# design.net
KiCad netlist of a schematic drawn in Altium Designer
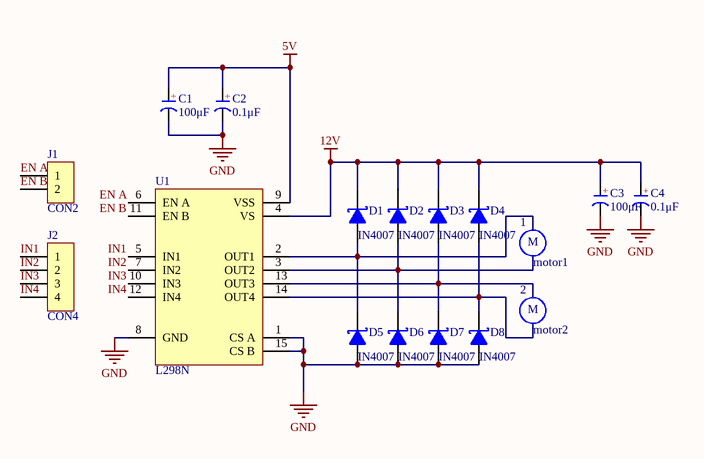
[diagram p0: 电机驱动原理图.SchDoc]

(export (version "E")
  (design (tool "Eeschema 10.0.6"))
  (components
    (comp (ref "1") (value "motor1") (libsource (lib "Schlib1") (part "电机")))
    (comp (ref "2") (value "motor2") (libsource (lib "Schlib1") (part "电机")))
    (comp (ref "C1") (value "100μF") (libsource (lib "Schlib1") (part "极性电容")))
    (comp (ref "C2") (value "0.1μF") (libsource (lib "Schlib1") (part "极性电容")))
    (comp (ref "C3") (value "100μF") (libsource (lib "Schlib1") (part "极性电容")))
    (comp (ref "C4") (value "0.1μF") (libsource (lib "Schlib1") (part "极性电容")))
    (comp (ref "D1") (value "IN4007") (libsource (lib "Schlib1") (part "肖特基二极管")))
    (comp (ref "D2") (value "IN4007") (libsource (lib "Schlib1") (part "肖特基二极管")))
    (comp (ref "D3") (value "IN4007") (libsource (lib "Schlib1") (part "肖特基二极管")))
    (comp (ref "D4") (value "IN4007") (libsource (lib "Schlib1") (part "肖特基二极管")))
    (comp (ref "D5") (value "IN4007") (libsource (lib "Schlib1") (part "肖特基二极管")))
    (comp (ref "D6") (value "IN4007") (libsource (lib "Schlib1") (part "肖特基二极管")))
    (comp (ref "D7") (value "IN4007") (libsource (lib "Schlib1") (part "肖特基二极管")))
    (comp (ref "D8") (value "IN4007") (libsource (lib "Schlib1") (part "肖特基二极管")))
    (comp (ref "J1")
      (value "CON2")
      (footprint "2PIN杜邦插座_1.27mm")
      (description "Connector")
      (libsource (lib "智能车主板") (part "CON2"))
    )
    (comp (ref "J2")
      (value "CON4")
      (footprint "HDR1X4")
      (description "Connector")
      (libsource (lib "智能车主板") (part "CON4"))
    )
    (comp (ref "U1") (value "L298N") (libsource (lib "Schlib1") (part "L298N")))
  )
  (nets
    (net (code "1") (name "/EN A") (class "Default")
      (node (ref "J1") (pin "1") (pinfunction "1_1") (pintype "passive"))
      (node (ref "U1") (pin "6") (pinfunction "EN_A_6") (pintype "passive"))
    )
    (net (code "2") (name "/EN B") (class "Default")
      (node (ref "J1") (pin "2") (pinfunction "2_2") (pintype "passive"))
      (node (ref "U1") (pin "11") (pinfunction "EN_B_11") (pintype "passive"))
    )
    (net (code "3") (name "/IN1") (class "Default")
      (node (ref "J2") (pin "1") (pinfunction "1_1") (pintype "passive"))
      (node (ref "U1") (pin "5") (pinfunction "IN1_5") (pintype "passive"))
    )
    (net (code "4") (name "/IN2") (class "Default")
      (node (ref "J2") (pin "2") (pinfunction "2_2") (pintype "passive"))
      (node (ref "U1") (pin "7") (pinfunction "IN2_7") (pintype "passive"))
    )
    (net (code "5") (name "/IN3") (class "Default")
      (node (ref "J2") (pin "3") (pinfunction "3_3") (pintype "passive"))
      (node (ref "U1") (pin "10") (pinfunction "IN3_10") (pintype "passive"))
    )
    (net (code "6") (name "/IN4") (class "Default")
      (node (ref "J2") (pin "4") (pinfunction "4_4") (pintype "passive"))
      (node (ref "U1") (pin "12") (pinfunction "IN4_12") (pintype "passive"))
    )
    (net (code "7") (name "5V") (class "Default")
      (node (ref "C1") (pin "1") (pinfunction "A_1") (pintype "passive"))
      (node (ref "C2") (pin "1") (pinfunction "A_1") (pintype "passive"))
      (node (ref "U1") (pin "9") (pinfunction "VSS_9") (pintype "passive"))
    )
    (net (code "8") (name "12V") (class "Default")
      (node (ref "C3") (pin "1") (pinfunction "A_1") (pintype "passive"))
      (node (ref "C4") (pin "1") (pinfunction "A_1") (pintype "passive"))
      (node (ref "D1") (pin "2") (pinfunction "K_2") (pintype "passive"))
      (node (ref "D2") (pin "2") (pinfunction "K_2") (pintype "passive"))
      (node (ref "D3") (pin "2") (pinfunction "K_2") (pintype "passive"))
      (node (ref "D4") (pin "2") (pinfunction "K_2") (pintype "passive"))
      (node (ref "U1") (pin "4") (pinfunction "VS_4") (pintype "passive"))
    )
    (net (code "9") (name "GND") (class "Default")
      (node (ref "C1") (pin "2") (pinfunction "K_2") (pintype "passive"))
      (node (ref "C2") (pin "2") (pinfunction "K_2") (pintype "passive"))
      (node (ref "C3") (pin "2") (pinfunction "K_2") (pintype "passive"))
      (node (ref "C4") (pin "2") (pinfunction "K_2") (pintype "passive"))
      (node (ref "D5") (pin "1") (pinfunction "A_1") (pintype "passive"))
      (node (ref "D6") (pin "1") (pinfunction "A_1") (pintype "passive"))
      (node (ref "D7") (pin "1") (pinfunction "A_1") (pintype "passive"))
      (node (ref "D8") (pin "1") (pinfunction "A_1") (pintype "passive"))
      (node (ref "U1") (pin "1") (pinfunction "CS_A_1") (pintype "passive"))
      (node (ref "U1") (pin "15") (pinfunction "CS_B_15") (pintype "passive"))
      (node (ref "U1") (pin "8") (pinfunction "GND_8") (pintype "passive"))
    )
    (net (code "10") (name "Net-(D1-A)") (class "Default")
      (node (ref "D1") (pin "1") (pinfunction "A_1") (pintype "passive"))
      (node (ref "D5") (pin "2") (pinfunction "K_2") (pintype "passive"))
      (node (ref "U1") (pin "2") (pinfunction "OUT1_2") (pintype "passive"))
    )
    (net (code "11") (name "Net-(D2-A)") (class "Default")
      (node (ref "D2") (pin "1") (pinfunction "A_1") (pintype "passive"))
      (node (ref "D6") (pin "2") (pinfunction "K_2") (pintype "passive"))
      (node (ref "U1") (pin "3") (pinfunction "OUT2_3") (pintype "passive"))
    )
    (net (code "12") (name "Net-(D3-A)") (class "Default")
      (node (ref "D3") (pin "1") (pinfunction "A_1") (pintype "passive"))
      (node (ref "D7") (pin "2") (pinfunction "K_2") (pintype "passive"))
      (node (ref "U1") (pin "13") (pinfunction "OUT3_13") (pintype "passive"))
    )
    (net (code "13") (name "Net-(D4-A)") (class "Default")
      (node (ref "D4") (pin "1") (pinfunction "A_1") (pintype "passive"))
      (node (ref "D8") (pin "2") (pinfunction "K_2") (pintype "passive"))
      (node (ref "U1") (pin "14") (pinfunction "OUT4_14") (pintype "passive"))
    )
  )
)
